# ArduinoMega2560-A4.net
KiCad netlist of a schematic drawn in Altium Designer
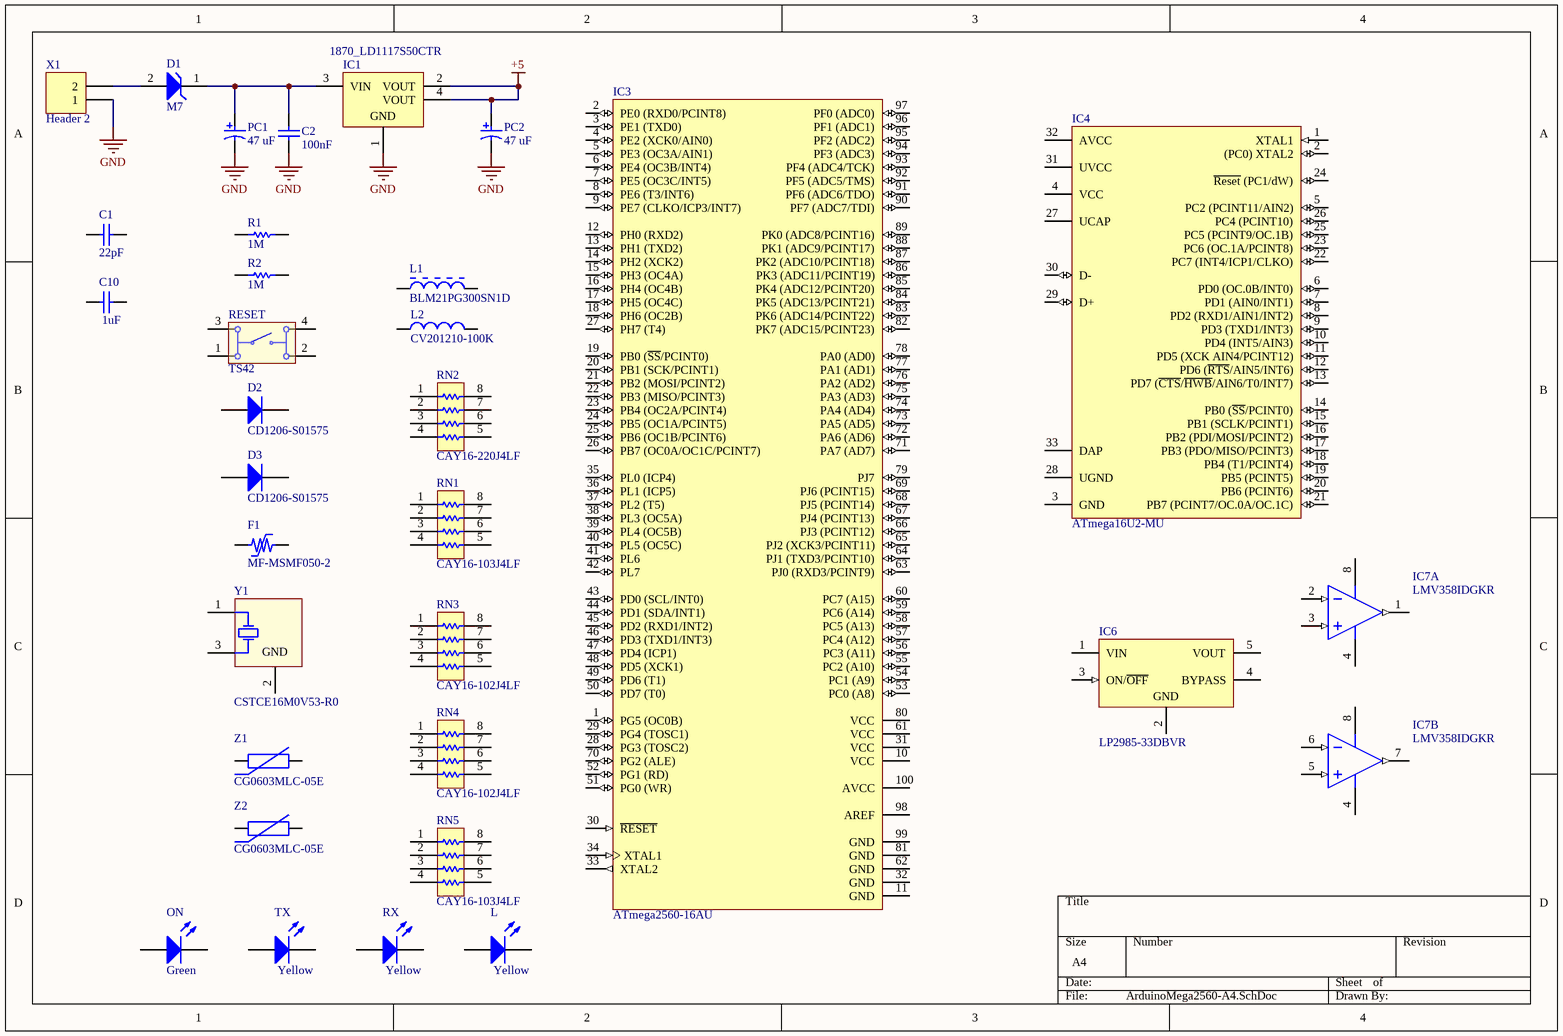
[diagram p0: ArduinoMega2560-A4.SchDoc]

(export (version "E")
  (design (tool "Eeschema 10.0.6"))
  (components
    (comp (ref "C1")
      (value "22pF")
      (footprint "CAPC1608X90X35ML10T15")
      (description "Chip Capacitor, 22 pF, +/- 5%, 50 V, -55 to 125 degC, 0603 (1608 Metric), RoHS, Tape and Reel")
      (fields (field (name "MANUFACTURER") "Murata"))
      (libsource (lib "Altium Content Vault") (part "CAP-NP-2"))
    )
    (comp (ref "C2")
      (value "100nF")
      (footprint "CAPC1608X90X20LL10")
      (description "Chip Capacitor, 0.1 uF, +/- 10%, 50 V, -55 to 125 degC, 0603 (1608 Metric), RoHS, Tape and Reel")
      (fields (field (name "VOLTAGE") "50V") (field (name "TOLERANCE") "10%"))
      (libsource (lib "Altium Content Vault") (part "CAP-NP-2"))
    )
    (comp (ref "C10")
      (value "1uF")
      (footprint "CAPC1608X90X35LL10T15")
      (fields (field (name "MANUFACTURER") "Murata") (field (name "PART NUMBER") "GRM188R61E105KA12D"))
      (libsource (lib "Altium Content Vault") (part "CAP"))
    )
    (comp (ref "D1")
      (value "M7")
      (footprint "ONSC-SMB-2-403A-03_H_V")
      (fields (field (name "PARTNUMBER") "1SMB24AT3G") (field (name "MANUFACTURER") "On Semiconductor"))
      (libsource (lib "Altium Content Vault") (part "ONSC-K1A2-2"))
    )
    (comp (ref "D2")
      (value "CD1206-S01575")
      (footprint "BOUR-CD1206-S01575-2_L")
      (description "75 V Small Signal Switching Diode, 150 mA, 2.5 uA, 1026 Molded Package, RoHS, Tape and Reel")
      (fields (field (name "MANUFACTURER") "Bourns"))
      (libsource (lib "Altium Content Vault") (part "BOUR-A1K2-2"))
    )
    (comp (ref "D3")
      (value "CD1206-S01575")
      (footprint "BOUR-CD1206-S01575-2_L")
      (description "75 V Small Signal Switching Diode, 150 mA, 2.5 uA, 1026 Molded Package, RoHS, Tape and Reel")
      (fields (field (name "MANUFACTURER") "Bourns"))
      (libsource (lib "Altium Content Vault") (part "BOUR-A1K2-2"))
    )
    (comp (ref "F1")
      (value "MF-MSMF050-2")
      (footprint "BOUR-MF-MSMF050-2_V")
      (description "PTC Resettable Fuse, 15 V, 500 mA, -40 to 85 degC, 2-Pin SMD, RoHS, Tape and Reel")
      (fields (field (name "MANUFACTURER") "Bourns"))
      (libsource (lib "Altium Content Vault") (part "PPTC-2"))
    )
    (comp (ref "IC1")
      (value "1870_LD1117S50CTR")
      (footprint "SOT-223_N")
      (libsource (lib "Altium Content Vault") (part "PM-REG-LD1117-SOT4"))
    )
    (comp (ref "IC3")
      (value "ATmega2560-16AU")
      (footprint "100A_M")
      (libsource (lib "Altium Content Vault") (part "MC-8B-ATM640-SQ100"))
    )
    (comp (ref "IC4")
      (value "ATmega16U2-MU")
      (footprint "32PG_N")
      (libsource (lib "Altium Content Vault") (part "MC-8B-ATM8U2-SQ33"))
    )
    (comp (ref "IC6")
      (value "LP2985-33DBVR")
      (footprint "DBV0005A_M")
      (fields (field (name "MANUFACTURER") "Texas Instruments"))
      (libsource (lib "Altium Content Vault") (part "TI-LP2985_A-10DBV5"))
    )
    (comp (ref "IC7")
      (value "LMV358IDGKR")
      (footprint "DGK0008A_M")
      (fields (field (name "MANUFACTURER") "Texas Instruments"))
      (libsource (lib "Altium Content Vault") (part "TI-LMV358-8"))
    )
    (comp (ref "L")
      (value "Yellow")
      (footprint "0805_A")
      (description "0044_KPT-2012YC\r\nLED YELLOW - SMD - 0805\r\nSMD mono-color Chip LED, WL-SMCW, Yellow")
      (fields (field (name "MANUFACTURER") "Wuerth Elektronik") (field (name "PARTNUMBER") "150080YS75000"))
      (libsource (lib "Altium Content Vault") (part "WE-LED_K1A2-2"))
    )
    (comp (ref "L1")
      (value "BLM21PG300SN1D")
      (footprint "MURA-BLM21-B40-CHIP-2_V3")
      (fields (field (name "MANUFACTURER") "Murata"))
      (libsource (lib "Altium Content Vault") (part "MURA-FB-2"))
    )
    (comp (ref "L2")
      (value "CV201210-100K")
      (footprint "MURA-IND0805_L")
      (description "Fixed Inductor, 10 uH, +/-20%, -55 to 125 degC, 2-Pin SMD (0805), RoHS, Tape and Reel")
      (fields (field (name "MANUFACTURER") "Murata"))
      (libsource (lib "Altium Content Vault") (part "IND-2"))
    )
    (comp (ref "ON")
      (value "Green")
      (footprint "0805_A")
      (description "KPT-2012SGC CHIPLED_0805 LED GREEN - SMD-0805\r\nSMD mono-color Chip LED, WL-SMCW, Green")
      (fields (field (name "PARTNUMBER") "150080GS75000") (field (name "MANUFACTURER") "Wuerth Elektronik"))
      (libsource (lib "Altium Content Vault") (part "WE-LED_K1A2-2"))
    )
    (comp (ref "PC1")
      (value "47 uF")
      (footprint "PNSC-FP-V-D_V")
      (fields (field (name "MANUFACTURER") "Panasonic"))
      (libsource (lib "Altium Content Vault") (part "CAP-P-2"))
    )
    (comp (ref "PC2")
      (value "47 uF")
      (footprint "PNSC-FP-V-D_V")
      (fields (field (name "MANUFACTURER") "Panasonic"))
      (libsource (lib "Altium Content Vault") (part "CAP-P-2"))
    )
    (comp (ref "R1")
      (value "1M")
      (footprint "RESC1609X50X30LL10T20")
      (fields (field (name "MANUFACTURER") "Vishay Dale") (field (name "PART NUMBER") "CRCW06031M00FKEA"))
      (libsource (lib "Altium Content Vault") (part "RES"))
    )
    (comp (ref "R2")
      (value "1M")
      (footprint "RESC1609X50X30LL10T20")
      (fields (field (name "MANUFACTURER") "Vishay Dale") (field (name "PART NUMBER") "CRCW06031M00FKEA"))
      (libsource (lib "Altium Content Vault") (part "RES"))
    )
    (comp (ref "RESET")
      (value "TS42")
      (footprint "430152070826")
      (description "WS-TASV SMD Tact Switch 6X6 mm")
      (fields (field (name "PARTNUMBER") "430152070826") (field (name "MANUFACTURER") "Wuerth Elektronik"))
      (libsource (lib "Altium Content Vault") (part "WE-TACT-SW-4"))
    )
    (comp (ref "RN1")
      (value "CAY16-103J4LF")
      (footprint "BOUR-CAY16-J4_V")
      (description "Chip Resistor Array, 10 KOhm, +/- 5%, 62.5 mW, -55 to 125 degC, 8-Pin SMD, RoHS, Tape and Reel")
      (fields (field (name "TOLERANCE") "1%"))
      (libsource (lib "Altium Content Vault") (part "RES-P-8"))
    )
    (comp (ref "RN2")
      (value "CAY16-220J4LF")
      (footprint "BOUR-CAY16-J4_V")
      (description "Chip Resistor Array, 22 Ohm, +/- 5%, 62.5 mW, -55 to 125 degC, 8-Pin SMD, RoHS, Tape and Reel")
      (fields (field (name "TOLERANCE") "1%"))
      (libsource (lib "Altium Content Vault") (part "RES-P-8"))
    )
    (comp (ref "RN3")
      (value "CAY16-102J4LF")
      (footprint "BOUR-CAY16-J4_V")
      (description "Chip Resistor Array, 1 KOhm, +/- 5%, 62.5 mW, -55 to 125 degC, 8-Pin SMD, RoHS, Tape and Reel")
      (fields (field (name "TOLERANCE") "1%"))
      (libsource (lib "Altium Content Vault") (part "RES-P-8"))
    )
    (comp (ref "RN4")
      (value "CAY16-102J4LF")
      (footprint "BOUR-CAY16-J4_V")
      (description "Chip Resistor Array, 1 KOhm, +/- 5%, 62.5 mW, -55 to 125 degC, 8-Pin SMD, RoHS, Tape and Reel")
      (fields (field (name "TOLERANCE") "1%"))
      (libsource (lib "Altium Content Vault") (part "RES-P-8"))
    )
    (comp (ref "RN5")
      (value "CAY16-103J4LF")
      (footprint "BOUR-CAY16-J4_V")
      (description "Chip Resistor Array, 10 KOhm, +/- 5%, 62.5 mW, -55 to 125 degC, 8-Pin SMD, RoHS, Tape and Reel")
      (fields (field (name "TOLERANCE") "1%"))
      (libsource (lib "Altium Content Vault") (part "RES-P-8"))
    )
    (comp (ref "RX")
      (value "Yellow")
      (footprint "0805_A")
      (description "0044_KPT-2012YC\r\nLED YELLOW - SMD - 0805\r\nSMD mono-color Chip LED, WL-SMCW, Yellow")
      (fields (field (name "MANUFACTURER") "Wuerth Elektronik") (field (name "PARTNUMBER") "150080YS75000"))
      (libsource (lib "Altium Content Vault") (part "WE-LED_K1A2-2"))
    )
    (comp (ref "TX")
      (value "Yellow")
      (footprint "0805_A")
      (description "0044_KPT-2012YC\r\nLED YELLOW - SMD - 0805\r\nSMD mono-color Chip LED, WL-SMCW, Yellow")
      (fields (field (name "MANUFACTURER") "Wuerth Elektronik") (field (name "PARTNUMBER") "150080YS75000"))
      (libsource (lib "Altium Content Vault") (part "WE-LED_K1A2-2"))
    )
    (comp (ref "X1")
      (value "Header 2")
      (footprint "HDR1X2")
      (description "Header, 2-Pin")
      (fields (field (name "PUBLISHER") "Altium Limited"))
      (libsource (lib "Miscellaneous Connectors") (part "Header 2"))
    )
    (comp (ref "Y1")
      (value "CSTCE16M0V53-R0")
      (footprint "MURA-CSTCE_V-3_V")
      (fields (field (name "MANUFACTURER") "Murata"))
      (libsource (lib "Altium Content Vault") (part "MURA-CSTCE_V-3"))
    )
    (comp (ref "Z1")
      (value "CG0603MLC-05E")
      (footprint "BOUR-CG0603-2_V")
      (description "ESD Protector, 5 V Supply, -40 to 85 degC, 1.6 x 0.8 x 0.55 mm SMD, RoHS, Tape and Reel")
      (fields (field (name "MANUFACTURER") "Bourns"))
      (libsource (lib "Altium Content Vault") (part "BOUR-VSR-2"))
    )
    (comp (ref "Z2")
      (value "CG0603MLC-05E")
      (footprint "BOUR-CG0603-2_V")
      (description "ESD Protector, 5 V Supply, -40 to 85 degC, 1.6 x 0.8 x 0.55 mm SMD, RoHS, Tape and Reel")
      (fields (field (name "MANUFACTURER") "Bourns"))
      (libsource (lib "Altium Content Vault") (part "BOUR-VSR-2"))
    )
  )
  (nets
    (net (code "1") (name "+5") (class "Default")
      (node (ref "IC1") (pin "2") (pinfunction "VOUT_2") (pintype "power_in"))
      (node (ref "IC1") (pin "4") (pinfunction "VOUT_4") (pintype "power_in"))
      (node (ref "PC2") (pin "1") (pinfunction "1_1") (pintype "passive"))
    )
    (net (code "2") (name "GND") (class "Default")
      (node (ref "C2") (pin "1") (pinfunction "1_1") (pintype "passive"))
      (node (ref "IC1") (pin "1") (pinfunction "GND_1") (pintype "power_in"))
      (node (ref "PC1") (pin "2") (pinfunction "2_2") (pintype "passive"))
      (node (ref "PC2") (pin "2") (pinfunction "2_2") (pintype "passive"))
      (node (ref "X1") (pin "1") (pinfunction "1_1") (pintype "passive"))
    )
    (net (code "3") (name "Net-(D1-A)") (class "Default")
      (node (ref "D1") (pin "2") (pinfunction "A_2") (pintype "passive"))
      (node (ref "X1") (pin "2") (pinfunction "2_2") (pintype "passive"))
    )
    (net (code "4") (name "Net-(D1-K)") (class "Default")
      (node (ref "C2") (pin "2") (pinfunction "2_2") (pintype "passive"))
      (node (ref "D1") (pin "1") (pinfunction "K_1") (pintype "passive"))
      (node (ref "IC1") (pin "3") (pinfunction "VIN_3") (pintype "power_in"))
      (node (ref "PC1") (pin "1") (pinfunction "1_1") (pintype "passive"))
    )
    (net (code "5") (name "unconnected-(C1-Pad1)") (class "Default")
      (node (ref "C1") (pin "1") (pinfunction "1_1") (pintype "passive"))
    )
    (net (code "6") (name "unconnected-(C1-Pad2)") (class "Default")
      (node (ref "C1") (pin "2") (pinfunction "2_2") (pintype "passive"))
    )
    (net (code "7") (name "unconnected-(C10-Pad1)") (class "Default")
      (node (ref "C10") (pin "1") (pinfunction "1_1") (pintype "passive"))
    )
    (net (code "8") (name "unconnected-(C10-Pad2)") (class "Default")
      (node (ref "C10") (pin "2") (pinfunction "2_2") (pintype "passive"))
    )
    (net (code "9") (name "unconnected-(D2-A-Pad1)") (class "Default")
      (node (ref "D2") (pin "1") (pinfunction "A_1") (pintype "passive"))
    )
    (net (code "10") (name "unconnected-(D2-K-Pad2)") (class "Default")
      (node (ref "D2") (pin "2") (pinfunction "K_2") (pintype "passive"))
    )
    (net (code "11") (name "unconnected-(D3-A-Pad1)") (class "Default")
      (node (ref "D3") (pin "1") (pinfunction "A_1") (pintype "passive"))
    )
    (net (code "12") (name "unconnected-(D3-K-Pad2)") (class "Default")
      (node (ref "D3") (pin "2") (pinfunction "K_2") (pintype "passive"))
    )
    (net (code "13") (name "unconnected-(F1-Pad1)") (class "Default")
      (node (ref "F1") (pin "1") (pinfunction "1_1") (pintype "passive"))
    )
    (net (code "14") (name "unconnected-(F1-Pad2)") (class "Default")
      (node (ref "F1") (pin "2") (pinfunction "2_2") (pintype "passive"))
    )
    (net (code "15") (name "unconnected-(IC3-AREF-Pad98)") (class "Default")
      (node (ref "IC3") (pin "98") (pinfunction "AREF_98") (pintype "power_in"))
    )
    (net (code "16") (name "unconnected-(IC3-AVCC-Pad100)") (class "Default")
      (node (ref "IC3") (pin "100") (pinfunction "AVCC_100") (pintype "power_in"))
    )
    (net (code "17") (name "unconnected-(IC3-GND-Pad11)") (class "Default")
      (node (ref "IC3") (pin "11") (pinfunction "GND_11") (pintype "power_in"))
    )
    (net (code "18") (name "unconnected-(IC3-GND-Pad32)") (class "Default")
      (node (ref "IC3") (pin "32") (pinfunction "GND_32") (pintype "power_in"))
    )
    (net (code "19") (name "unconnected-(IC3-GND-Pad62)") (class "Default")
      (node (ref "IC3") (pin "62") (pinfunction "GND_62") (pintype "power_in"))
    )
    (net (code "20") (name "unconnected-(IC3-GND-Pad81)") (class "Default")
      (node (ref "IC3") (pin "81") (pinfunction "GND_81") (pintype "power_in"))
    )
    (net (code "21") (name "unconnected-(IC3-GND-Pad99)") (class "Default")
      (node (ref "IC3") (pin "99") (pinfunction "GND_99") (pintype "power_in"))
    )
    (net (code "22") (name "unconnected-(IC3-PA0_(AD0)-Pad78)") (class "Default")
      (node (ref "IC3") (pin "78") (pinfunction "PA0_(AD0)_78") (pintype "bidirectional"))
    )
    (net (code "23") (name "unconnected-(IC3-PA1_(AD1)-Pad77)") (class "Default")
      (node (ref "IC3") (pin "77") (pinfunction "PA1_(AD1)_77") (pintype "bidirectional"))
    )
    (net (code "24") (name "unconnected-(IC3-PA2_(AD2)-Pad76)") (class "Default")
      (node (ref "IC3") (pin "76") (pinfunction "PA2_(AD2)_76") (pintype "bidirectional"))
    )
    (net (code "25") (name "unconnected-(IC3-PA3_(AD3)-Pad75)") (class "Default")
      (node (ref "IC3") (pin "75") (pinfunction "PA3_(AD3)_75") (pintype "bidirectional"))
    )
    (net (code "26") (name "unconnected-(IC3-PA4_(AD4)-Pad74)") (class "Default")
      (node (ref "IC3") (pin "74") (pinfunction "PA4_(AD4)_74") (pintype "bidirectional"))
    )
    (net (code "27") (name "unconnected-(IC3-PA5_(AD5)-Pad73)") (class "Default")
      (node (ref "IC3") (pin "73") (pinfunction "PA5_(AD5)_73") (pintype "bidirectional"))
    )
    (net (code "28") (name "unconnected-(IC3-PA6_(AD6)-Pad72)") (class "Default")
      (node (ref "IC3") (pin "72") (pinfunction "PA6_(AD6)_72") (pintype "bidirectional"))
    )
    (net (code "29") (name "unconnected-(IC3-PA7_(AD7)-Pad71)") (class "Default")
      (node (ref "IC3") (pin "71") (pinfunction "PA7_(AD7)_71") (pintype "bidirectional"))
    )
    (net (code "30") (name "unconnected-(IC3-PB0_(~{SS}{slash}PCINT0)-Pad19)") (class "Default")
      (node (ref "IC3") (pin "19") (pinfunction "PB0_(~{SS}/PCINT0)_19") (pintype "bidirectional"))
    )
    (net (code "31") (name "unconnected-(IC3-PB1_(SCK{slash}PCINT1)-Pad20)") (class "Default")
      (node (ref "IC3") (pin "20") (pinfunction "PB1_(SCK/PCINT1)_20") (pintype "bidirectional"))
    )
    (net (code "32") (name "unconnected-(IC3-PB2_(MOSI{slash}PCINT2)-Pad21)") (class "Default")
      (node (ref "IC3") (pin "21") (pinfunction "PB2_(MOSI/PCINT2)_21") (pintype "bidirectional"))
    )
    (net (code "33") (name "unconnected-(IC3-PB3_(MISO{slash}PCINT3)-Pad22)") (class "Default")
      (node (ref "IC3") (pin "22") (pinfunction "PB3_(MISO/PCINT3)_22") (pintype "bidirectional"))
    )
    (net (code "34") (name "unconnected-(IC3-PB4_(OC2A{slash}PCINT4)-Pad23)") (class "Default")
      (node (ref "IC3") (pin "23") (pinfunction "PB4_(OC2A/PCINT4)_23") (pintype "bidirectional"))
    )
    (net (code "35") (name "unconnected-(IC3-PB5_(OC1A{slash}PCINT5)-Pad24)") (class "Default")
      (node (ref "IC3") (pin "24") (pinfunction "PB5_(OC1A/PCINT5)_24") (pintype "bidirectional"))
    )
    (net (code "36") (name "unconnected-(IC3-PB6_(OC1B{slash}PCINT6)-Pad25)") (class "Default")
      (node (ref "IC3") (pin "25") (pinfunction "PB6_(OC1B/PCINT6)_25") (pintype "bidirectional"))
    )
    (net (code "37") (name "unconnected-(IC3-PB7_(OC0A{slash}OC1C{slash}PCINT7)-Pad26)") (class "Default")
      (node (ref "IC3") (pin "26") (pinfunction "PB7_(OC0A/OC1C/PCINT7)_26") (pintype "bidirectional"))
    )
    (net (code "38") (name "unconnected-(IC3-PC0_(A8)-Pad53)") (class "Default")
      (node (ref "IC3") (pin "53") (pinfunction "PC0_(A8)_53") (pintype "bidirectional"))
    )
    (net (code "39") (name "unconnected-(IC3-PC1_(A9)-Pad54)") (class "Default")
      (node (ref "IC3") (pin "54") (pinfunction "PC1_(A9)_54") (pintype "bidirectional"))
    )
    (net (code "40") (name "unconnected-(IC3-PC2_(A10)-Pad55)") (class "Default")
      (node (ref "IC3") (pin "55") (pinfunction "PC2_(A10)_55") (pintype "bidirectional"))
    )
    (net (code "41") (name "unconnected-(IC3-PC3_(A11)-Pad56)") (class "Default")
      (node (ref "IC3") (pin "56") (pinfunction "PC3_(A11)_56") (pintype "bidirectional"))
    )
    (net (code "42") (name "unconnected-(IC3-PC4_(A12)-Pad57)") (class "Default")
      (node (ref "IC3") (pin "57") (pinfunction "PC4_(A12)_57") (pintype "bidirectional"))
    )
    (net (code "43") (name "unconnected-(IC3-PC5_(A13)-Pad58)") (class "Default")
      (node (ref "IC3") (pin "58") (pinfunction "PC5_(A13)_58") (pintype "bidirectional"))
    )
    (net (code "44") (name "unconnected-(IC3-PC6_(A14)-Pad59)") (class "Default")
      (node (ref "IC3") (pin "59") (pinfunction "PC6_(A14)_59") (pintype "bidirectional"))
    )
    (net (code "45") (name "unconnected-(IC3-PC7_(A15)-Pad60)") (class "Default")
      (node (ref "IC3") (pin "60") (pinfunction "PC7_(A15)_60") (pintype "bidirectional"))
    )
    (net (code "46") (name "unconnected-(IC3-PD0_(SCL{slash}INT0)-Pad43)") (class "Default")
      (node (ref "IC3") (pin "43") (pinfunction "PD0_(SCL/INT0)_43") (pintype "bidirectional"))
    )
    (net (code "47") (name "unconnected-(IC3-PD1_(SDA{slash}INT1)-Pad44)") (class "Default")
      (node (ref "IC3") (pin "44") (pinfunction "PD1_(SDA/INT1)_44") (pintype "bidirectional"))
    )
    (net (code "48") (name "unconnected-(IC3-PD2_(RXD1{slash}INT2)-Pad45)") (class "Default")
      (node (ref "IC3") (pin "45") (pinfunction "PD2_(RXD1/INT2)_45") (pintype "bidirectional"))
    )
    (net (code "49") (name "unconnected-(IC3-PD3_(TXD1{slash}INT3)-Pad46)") (class "Default")
      (node (ref "IC3") (pin "46") (pinfunction "PD3_(TXD1/INT3)_46") (pintype "bidirectional"))
    )
    (net (code "50") (name "unconnected-(IC3-PD4_(ICP1)-Pad47)") (class "Default")
      (node (ref "IC3") (pin "47") (pinfunction "PD4_(ICP1)_47") (pintype "bidirectional"))
    )
    (net (code "51") (name "unconnected-(IC3-PD5_(XCK1)-Pad48)") (class "Default")
      (node (ref "IC3") (pin "48") (pinfunction "PD5_(XCK1)_48") (pintype "bidirectional"))
    )
    (net (code "52") (name "unconnected-(IC3-PD6_(T1)-Pad49)") (class "Default")
      (node (ref "IC3") (pin "49") (pinfunction "PD6_(T1)_49") (pintype "bidirectional"))
    )
    (net (code "53") (name "unconnected-(IC3-PD7_(T0)-Pad50)") (class "Default")
      (node (ref "IC3") (pin "50") (pinfunction "PD7_(T0)_50") (pintype "bidirectional"))
    )
    (net (code "54") (name "unconnected-(IC3-PE0_(RXD0{slash}PCINT8)-Pad2)") (class "Default")
      (node (ref "IC3") (pin "2") (pinfunction "PE0_(RXD0/PCINT8)_2") (pintype "bidirectional"))
    )
    (net (code "55") (name "unconnected-(IC3-PE1_(TXD0)-Pad3)") (class "Default")
      (node (ref "IC3") (pin "3") (pinfunction "PE1_(TXD0)_3") (pintype "bidirectional"))
    )
    (net (code "56") (name "unconnected-(IC3-PE2_(XCK0{slash}AIN0)-Pad4)") (class "Default")
      (node (ref "IC3") (pin "4") (pinfunction "PE2_(XCK0/AIN0)_4") (pintype "bidirectional"))
    )
    (net (code "57") (name "unconnected-(IC3-PE3_(OC3A{slash}AIN1)-Pad5)") (class "Default")
      (node (ref "IC3") (pin "5") (pinfunction "PE3_(OC3A/AIN1)_5") (pintype "bidirectional"))
    )
    (net (code "58") (name "unconnected-(IC3-PE4_(OC3B{slash}INT4)-Pad6)") (class "Default")
      (node (ref "IC3") (pin "6") (pinfunction "PE4_(OC3B/INT4)_6") (pintype "bidirectional"))
    )
    (net (code "59") (name "unconnected-(IC3-PE5_(OC3C{slash}INT5)-Pad7)") (class "Default")
      (node (ref "IC3") (pin "7") (pinfunction "PE5_(OC3C/INT5)_7") (pintype "bidirectional"))
    )
    (net (code "60") (name "unconnected-(IC3-PE6_(T3{slash}INT6)-Pad8)") (class "Default")
      (node (ref "IC3") (pin "8") (pinfunction "PE6_(T3/INT6)_8") (pintype "bidirectional"))
    )
    (net (code "61") (name "unconnected-(IC3-PE7_(CLKO{slash}ICP3{slash}INT7)-Pad9)") (class "Default")
      (node (ref "IC3") (pin "9") (pinfunction "PE7_(CLKO/ICP3/INT7)_9") (pintype "bidirectional"))
    )
    (net (code "62") (name "unconnected-(IC3-PF0_(ADC0)-Pad97)") (class "Default")
      (node (ref "IC3") (pin "97") (pinfunction "PF0_(ADC0)_97") (pintype "bidirectional"))
    )
    (net (code "63") (name "unconnected-(IC3-PF1_(ADC1)-Pad96)") (class "Default")
      (node (ref "IC3") (pin "96") (pinfunction "PF1_(ADC1)_96") (pintype "bidirectional"))
    )
    (net (code "64") (name "unconnected-(IC3-PF2_(ADC2)-Pad95)") (class "Default")
      (node (ref "IC3") (pin "95") (pinfunction "PF2_(ADC2)_95") (pintype "bidirectional"))
    )
    (net (code "65") (name "unconnected-(IC3-PF3_(ADC3)-Pad94)") (class "Default")
      (node (ref "IC3") (pin "94") (pinfunction "PF3_(ADC3)_94") (pintype "bidirectional"))
    )
    (net (code "66") (name "unconnected-(IC3-PF4_(ADC4{slash}TCK)-Pad93)") (class "Default")
      (node (ref "IC3") (pin "93") (pinfunction "PF4_(ADC4/TCK)_93") (pintype "bidirectional"))
    )
    (net (code "67") (name "unconnected-(IC3-PF5_(ADC5{slash}TMS)-Pad92)") (class "Default")
      (node (ref "IC3") (pin "92") (pinfunction "PF5_(ADC5/TMS)_92") (pintype "bidirectional"))
    )
    (net (code "68") (name "unconnected-(IC3-PF6_(ADC6{slash}TDO)-Pad91)") (class "Default")
      (node (ref "IC3") (pin "91") (pinfunction "PF6_(ADC6/TDO)_91") (pintype "bidirectional"))
    )
    (net (code "69") (name "unconnected-(IC3-PF7_(ADC7{slash}TDI)-Pad90)") (class "Default")
      (node (ref "IC3") (pin "90") (pinfunction "PF7_(ADC7/TDI)_90") (pintype "bidirectional"))
    )
    (net (code "70") (name "unconnected-(IC3-PG0_(WR)-Pad51)") (class "Default")
      (node (ref "IC3") (pin "51") (pinfunction "PG0_(WR)_51") (pintype "bidirectional"))
    )
    (net (code "71") (name "unconnected-(IC3-PG1_(RD)-Pad52)") (class "Default")
      (node (ref "IC3") (pin "52") (pinfunction "PG1_(RD)_52") (pintype "bidirectional"))
    )
    (net (code "72") (name "unconnected-(IC3-PG2_(ALE)-Pad70)") (class "Default")
      (node (ref "IC3") (pin "70") (pinfunction "PG2_(ALE)_70") (pintype "bidirectional"))
    )
    (net (code "73") (name "unconnected-(IC3-PG3_(TOSC2)-Pad28)") (class "Default")
      (node (ref "IC3") (pin "28") (pinfunction "PG3_(TOSC2)_28") (pintype "bidirectional"))
    )
    (net (code "74") (name "unconnected-(IC3-PG4_(TOSC1)-Pad29)") (class "Default")
      (node (ref "IC3") (pin "29") (pinfunction "PG4_(TOSC1)_29") (pintype "bidirectional"))
    )
    (net (code "75") (name "unconnected-(IC3-PG5_(OC0B)-Pad1)") (class "Default")
      (node (ref "IC3") (pin "1") (pinfunction "PG5_(OC0B)_1") (pintype "bidirectional"))
    )
    (net (code "76") (name "unconnected-(IC3-PH0_(RXD2)-Pad12)") (class "Default")
      (node (ref "IC3") (pin "12") (pinfunction "PH0_(RXD2)_12") (pintype "bidirectional"))
    )
    (net (code "77") (name "unconnected-(IC3-PH1_(TXD2)-Pad13)") (class "Default")
      (node (ref "IC3") (pin "13") (pinfunction "PH1_(TXD2)_13") (pintype "bidirectional"))
    )
    (net (code "78") (name "unconnected-(IC3-PH2_(XCK2)-Pad14)") (class "Default")
      (node (ref "IC3") (pin "14") (pinfunction "PH2_(XCK2)_14") (pintype "bidirectional"))
    )
    (net (code "79") (name "unconnected-(IC3-PH3_(OC4A)-Pad15)") (class "Default")
      (node (ref "IC3") (pin "15") (pinfunction "PH3_(OC4A)_15") (pintype "bidirectional"))
    )
    (net (code "80") (name "unconnected-(IC3-PH4_(OC4B)-Pad16)") (class "Default")
      (node (ref "IC3") (pin "16") (pinfunction "PH4_(OC4B)_16") (pintype "bidirectional"))
    )
    (net (code "81") (name "unconnected-(IC3-PH5_(OC4C)-Pad17)") (class "Default")
      (node (ref "IC3") (pin "17") (pinfunction "PH5_(OC4C)_17") (pintype "bidirectional"))
    )
    (net (code "82") (name "unconnected-(IC3-PH6_(OC2B)-Pad18)") (class "Default")
      (node (ref "IC3") (pin "18") (pinfunction "PH6_(OC2B)_18") (pintype "bidirectional"))
    )
    (net (code "83") (name "unconnected-(IC3-PH7_(T4)-Pad27)") (class "Default")
      (node (ref "IC3") (pin "27") (pinfunction "PH7_(T4)_27") (pintype "bidirectional"))
    )
    (net (code "84") (name "unconnected-(IC3-PJ0_(RXD3{slash}PCINT9)-Pad63)") (class "Default")
      (node (ref "IC3") (pin "63") (pinfunction "PJ0_(RXD3/PCINT9)_63") (pintype "bidirectional"))
    )
    (net (code "85") (name "unconnected-(IC3-PJ1_(TXD3{slash}PCINT10)-Pad64)") (class "Default")
      (node (ref "IC3") (pin "64") (pinfunction "PJ1_(TXD3/PCINT10)_64") (pintype "bidirectional"))
    )
    (net (code "86") (name "unconnected-(IC3-PJ2_(XCK3{slash}PCINT11)-Pad65)") (class "Default")
      (node (ref "IC3") (pin "65") (pinfunction "PJ2_(XCK3/PCINT11)_65") (pintype "bidirectional"))
    )
    (net (code "87") (name "unconnected-(IC3-PJ3_(PCINT12)-Pad66)") (class "Default")
      (node (ref "IC3") (pin "66") (pinfunction "PJ3_(PCINT12)_66") (pintype "bidirectional"))
    )
    (net (code "88") (name "unconnected-(IC3-PJ4_(PCINT13)-Pad67)") (class "Default")
      (node (ref "IC3") (pin "67") (pinfunction "PJ4_(PCINT13)_67") (pintype "bidirectional"))
    )
    (net (code "89") (name "unconnected-(IC3-PJ5_(PCINT14)-Pad68)") (class "Default")
      (node (ref "IC3") (pin "68") (pinfunction "PJ5_(PCINT14)_68") (pintype "bidirectional"))
    )
    (net (code "90") (name "unconnected-(IC3-PJ6_(PCINT15)-Pad69)") (class "Default")
      (node (ref "IC3") (pin "69") (pinfunction "PJ6_(PCINT15)_69") (pintype "bidirectional"))
    )
    (net (code "91") (name "unconnected-(IC3-PJ7-Pad79)") (class "Default")
      (node (ref "IC3") (pin "79") (pinfunction "PJ7_79") (pintype "bidirectional"))
    )
    (net (code "92") (name "unconnected-(IC3-PK0_(ADC8{slash}PCINT16)-Pad89)") (class "Default")
      (node (ref "IC3") (pin "89") (pinfunction "PK0_(ADC8/PCINT16)_89") (pintype "bidirectional"))
    )
    (net (code "93") (name "unconnected-(IC3-PK1_(ADC9{slash}PCINT17)-Pad88)") (class "Default")
      (node (ref "IC3") (pin "88") (pinfunction "PK1_(ADC9/PCINT17)_88") (pintype "bidirectional"))
    )
    (net (code "94") (name "unconnected-(IC3-PK2_(ADC10{slash}PCINT18)-Pad87)") (class "Default")
      (node (ref "IC3") (pin "87") (pinfunction "PK2_(ADC10/PCINT18)_87") (pintype "bidirectional"))
    )
    (net (code "95") (name "unconnected-(IC3-PK3_(ADC11{slash}PCINT19)-Pad86)") (class "Default")
      (node (ref "IC3") (pin "86") (pinfunction "PK3_(ADC11/PCINT19)_86") (pintype "bidirectional"))
    )
    (net (code "96") (name "unconnected-(IC3-PK4_(ADC12{slash}PCINT20)-Pad85)") (class "Default")
      (node (ref "IC3") (pin "85") (pinfunction "PK4_(ADC12/PCINT20)_85") (pintype "bidirectional"))
    )
    (net (code "97") (name "unconnected-(IC3-PK5_(ADC13{slash}PCINT21)-Pad84)") (class "Default")
      (node (ref "IC3") (pin "84") (pinfunction "PK5_(ADC13/PCINT21)_84") (pintype "bidirectional"))
    )
    (net (code "98") (name "unconnected-(IC3-PK6_(ADC14{slash}PCINT22)-Pad83)") (class "Default")
      (node (ref "IC3") (pin "83") (pinfunction "PK6_(ADC14/PCINT22)_83") (pintype "bidirectional"))
    )
    (net (code "99") (name "unconnected-(IC3-PK7_(ADC15{slash}PCINT23)-Pad82)") (class "Default")
      (node (ref "IC3") (pin "82") (pinfunction "PK7_(ADC15/PCINT23)_82") (pintype "bidirectional"))
    )
    (net (code "100") (name "unconnected-(IC3-PL0_(ICP4)-Pad35)") (class "Default")
      (node (ref "IC3") (pin "35") (pinfunction "PL0_(ICP4)_35") (pintype "bidirectional"))
    )
    (net (code "101") (name "unconnected-(IC3-PL1_(ICP5)-Pad36)") (class "Default")
      (node (ref "IC3") (pin "36") (pinfunction "PL1_(ICP5)_36") (pintype "bidirectional"))
    )
    (net (code "102") (name "unconnected-(IC3-PL2_(T5)-Pad37)") (class "Default")
      (node (ref "IC3") (pin "37") (pinfunction "PL2_(T5)_37") (pintype "bidirectional"))
    )
    (net (code "103") (name "unconnected-(IC3-PL3_(OC5A)-Pad38)") (class "Default")
      (node (ref "IC3") (pin "38") (pinfunction "PL3_(OC5A)_38") (pintype "bidirectional"))
    )
    (net (code "104") (name "unconnected-(IC3-PL4_(OC5B)-Pad39)") (class "Default")
      (node (ref "IC3") (pin "39") (pinfunction "PL4_(OC5B)_39") (pintype "bidirectional"))
    )
    (net (code "105") (name "unconnected-(IC3-PL5_(OC5C)-Pad40)") (class "Default")
      (node (ref "IC3") (pin "40") (pinfunction "PL5_(OC5C)_40") (pintype "bidirectional"))
    )
    (net (code "106") (name "unconnected-(IC3-PL6-Pad41)") (class "Default")
      (node (ref "IC3") (pin "41") (pinfunction "PL6_41") (pintype "bidirectional"))
    )
    (net (code "107") (name "unconnected-(IC3-PL7-Pad42)") (class "Default")
      (node (ref "IC3") (pin "42") (pinfunction "PL7_42") (pintype "bidirectional"))
    )
    (net (code "108") (name "unconnected-(IC3-VCC-Pad10)") (class "Default")
      (node (ref "IC3") (pin "10") (pinfunction "VCC_10") (pintype "power_in"))
    )
    (net (code "109") (name "unconnected-(IC3-VCC-Pad31)") (class "Default")
      (node (ref "IC3") (pin "31") (pinfunction "VCC_31") (pintype "power_in"))
    )
    (net (code "110") (name "unconnected-(IC3-VCC-Pad61)") (class "Default")
      (node (ref "IC3") (pin "61") (pinfunction "VCC_61") (pintype "power_in"))
    )
    (net (code "111") (name "unconnected-(IC3-VCC-Pad80)") (class "Default")
      (node (ref "IC3") (pin "80") (pinfunction "VCC_80") (pintype "power_in"))
    )
    (net (code "112") (name "unconnected-(IC3-XTAL1-Pad34)") (class "Default")
      (node (ref "IC3") (pin "34") (pinfunction "XTAL1_34") (pintype "input"))
    )
    (net (code "113") (name "unconnected-(IC3-XTAL2-Pad33)") (class "Default")
      (node (ref "IC3") (pin "33") (pinfunction "XTAL2_33") (pintype "output"))
    )
    (net (code "114") (name "unconnected-(IC3-~{RESET}-Pad30)") (class "Default")
      (node (ref "IC3") (pin "30") (pinfunction "~{RESET}_30") (pintype "input"))
    )
    (net (code "115") (name "unconnected-(IC4-(PC0)_XTAL2-Pad2)") (class "Default")
      (node (ref "IC4") (pin "2") (pinfunction "(PC0)_XTAL2_2") (pintype "bidirectional"))
    )
    (net (code "116") (name "unconnected-(IC4-AVCC-Pad32)") (class "Default")
      (node (ref "IC4") (pin "32") (pinfunction "AVCC_32") (pintype "power_in"))
    )
    (net (code "117") (name "unconnected-(IC4-D+-Pad29)") (class "Default")
      (node (ref "IC4") (pin "29") (pinfunction "D+_29") (pintype "bidirectional"))
    )
    (net (code "118") (name "unconnected-(IC4-D--Pad30)") (class "Default")
      (node (ref "IC4") (pin "30") (pinfunction "D-_30") (pintype "bidirectional"))
    )
    (net (code "119") (name "unconnected-(IC4-DAP-Pad33)") (class "Default")
      (node (ref "IC4") (pin "33") (pinfunction "DAP_33") (pintype "power_in"))
    )
    (net (code "120") (name "unconnected-(IC4-GND-Pad3)") (class "Default")
      (node (ref "IC4") (pin "3") (pinfunction "GND_3") (pintype "power_in"))
    )
    (net (code "121") (name "unconnected-(IC4-PB0_(~{SS}{slash}PCINT0)-Pad14)") (class "Default")
      (node (ref "IC4") (pin "14") (pinfunction "PB0_(~{SS}/PCINT0)_14") (pintype "bidirectional"))
    )
    (net (code "122") (name "unconnected-(IC4-PB1_(SCLK{slash}PCINT1)-Pad15)") (class "Default")
      (node (ref "IC4") (pin "15") (pinfunction "PB1_(SCLK/PCINT1)_15") (pintype "bidirectional"))
    )
    (net (code "123") (name "unconnected-(IC4-PB2_(PDI{slash}MOSI{slash}PCINT2)-Pad16)") (class "Default")
      (node (ref "IC4") (pin "16") (pinfunction "PB2_(PDI/MOSI/PCINT2)_16") (pintype "bidirectional"))
    )
    (net (code "124") (name "unconnected-(IC4-PB3_(PDO{slash}MISO{slash}PCINT3)-Pad17)") (class "Default")
      (node (ref "IC4") (pin "17") (pinfunction "PB3_(PDO/MISO/PCINT3)_17") (pintype "bidirectional"))
    )
    (net (code "125") (name "unconnected-(IC4-PB4_(T1{slash}PCINT4)-Pad18)") (class "Default")
      (node (ref "IC4") (pin "18") (pinfunction "PB4_(T1/PCINT4)_18") (pintype "bidirectional"))
    )
    (net (code "126") (name "unconnected-(IC4-PB5_(PCINT5)-Pad19)") (class "Default")
      (node (ref "IC4") (pin "19") (pinfunction "PB5_(PCINT5)_19") (pintype "bidirectional"))
    )
    (net (code "127") (name "unconnected-(IC4-PB6_(PCINT6)-Pad20)") (class "Default")
      (node (ref "IC4") (pin "20") (pinfunction "PB6_(PCINT6)_20") (pintype "bidirectional"))
    )
    (net (code "128") (name "unconnected-(IC4-PB7_(PCINT7{slash}OC.0A{slash}OC.1C)-Pad21)") (class "Default")
      (node (ref "IC4") (pin "21") (pinfunction "PB7_(PCINT7/OC.0A/OC.1C)_21") (pintype "bidirectional"))
    )
    (net (code "129") (name "unconnected-(IC4-PC2_(PCINT11{slash}AIN2)-Pad5)") (class "Default")
      (node (ref "IC4") (pin "5") (pinfunction "PC2_(PCINT11/AIN2)_5") (pintype "bidirectional"))
    )
    (net (code "130") (name "unconnected-(IC4-PC4_(PCINT10)-Pad26)") (class "Default")
      (node (ref "IC4") (pin "26") (pinfunction "PC4_(PCINT10)_26") (pintype "bidirectional"))
    )
    (net (code "131") (name "unconnected-(IC4-PC5_(PCINT9{slash}OC.1B)-Pad25)") (class "Default")
      (node (ref "IC4") (pin "25") (pinfunction "PC5_(PCINT9/OC.1B)_25") (pintype "bidirectional"))
    )
    (net (code "132") (name "unconnected-(IC4-PC6_(OC.1A{slash}PCINT8)-Pad23)") (class "Default")
      (node (ref "IC4") (pin "23") (pinfunction "PC6_(OC.1A/PCINT8)_23") (pintype "bidirectional"))
    )
    (net (code "133") (name "unconnected-(IC4-PC7_(INT4{slash}ICP1{slash}CLKO)-Pad22)") (class "Default")
      (node (ref "IC4") (pin "22") (pinfunction "PC7_(INT4/ICP1/CLKO)_22") (pintype "bidirectional"))
    )
    (net (code "134") (name "unconnected-(IC4-PD0_(OC.0B{slash}INT0)-Pad6)") (class "Default")
      (node (ref "IC4") (pin "6") (pinfunction "PD0_(OC.0B/INT0)_6") (pintype "bidirectional"))
    )
    (net (code "135") (name "unconnected-(IC4-PD1_(AIN0{slash}INT1)-Pad7)") (class "Default")
      (node (ref "IC4") (pin "7") (pinfunction "PD1_(AIN0/INT1)_7") (pintype "bidirectional"))
    )
    (net (code "136") (name "unconnected-(IC4-PD2_(RXD1{slash}AIN1{slash}INT2)-Pad8)") (class "Default")
      (node (ref "IC4") (pin "8") (pinfunction "PD2_(RXD1/AIN1/INT2)_8") (pintype "bidirectional"))
    )
    (net (code "137") (name "unconnected-(IC4-PD3_(TXD1{slash}INT3)-Pad9)") (class "Default")
      (node (ref "IC4") (pin "9") (pinfunction "PD3_(TXD1/INT3)_9") (pintype "bidirectional"))
    )
    (net (code "138") (name "unconnected-(IC4-PD4_(INT5{slash}AIN3)-Pad10)") (class "Default")
      (node (ref "IC4") (pin "10") (pinfunction "PD4_(INT5/AIN3)_10") (pintype "bidirectional"))
    )
    (net (code "139") (name "unconnected-(IC4-PD5_(XCK_AIN4{slash}PCINT12)-Pad11)") (class "Default")
      (node (ref "IC4") (pin "11") (pinfunction "PD5_(XCK_AIN4/PCINT12)_11") (pintype "bidirectional"))
    )
    (net (code "140") (name "unconnected-(IC4-PD6_(~{RTS}{slash}AIN5{slash}INT6)-Pad12)") (class "Default")
      (node (ref "IC4") (pin "12") (pinfunction "PD6_(~{RTS}/AIN5/INT6)_12") (pintype "bidirectional"))
    )
    (net (code "141") (name "unconnected-(IC4-PD7_(~{CTS}{slash}~{HWB}{slash}AIN6{slash}T0{slash}INT7)-Pad13)") (class "Default")
      (node (ref "IC4") (pin "13") (pinfunction "PD7_(~{CTS}/~{HWB}/AIN6/T0/INT7)_13") (pintype "bidirectional"))
    )
    (net (code "142") (name "unconnected-(IC4-UCAP-Pad27)") (class "Default")
      (node (ref "IC4") (pin "27") (pinfunction "UCAP_27") (pintype "power_in"))
    )
    (net (code "143") (name "unconnected-(IC4-UGND-Pad28)") (class "Default")
      (node (ref "IC4") (pin "28") (pinfunction "UGND_28") (pintype "power_in"))
    )
    (net (code "144") (name "unconnected-(IC4-UVCC-Pad31)") (class "Default")
      (node (ref "IC4") (pin "31") (pinfunction "UVCC_31") (pintype "power_in"))
    )
    (net (code "145") (name "unconnected-(IC4-VCC-Pad4)") (class "Default")
      (node (ref "IC4") (pin "4") (pinfunction "VCC_4") (pintype "power_in"))
    )
    (net (code "146") (name "unconnected-(IC4-XTAL1-Pad1)") (class "Default")
      (node (ref "IC4") (pin "1") (pinfunction "XTAL1_1") (pintype "input"))
    )
    (net (code "147") (name "unconnected-(IC4-~{Reset}_(PC1{slash}dW)-Pad24)") (class "Default")
      (node (ref "IC4") (pin "24") (pinfunction "~{Reset}_(PC1/dW)_24") (pintype "bidirectional"))
    )
    (net (code "148") (name "unconnected-(IC6-BYPASS-Pad4)") (class "Default")
      (node (ref "IC6") (pin "4") (pinfunction "BYPASS_4") (pintype "passive"))
    )
    (net (code "149") (name "unconnected-(IC6-GND-Pad2)") (class "Default")
      (node (ref "IC6") (pin "2") (pinfunction "GND_2") (pintype "power_in"))
    )
    (net (code "150") (name "unconnected-(IC6-ON{slash}~{OFF}-Pad3)") (class "Default")
      (node (ref "IC6") (pin "3") (pinfunction "ON/~{OFF}_3") (pintype "input"))
    )
    (net (code "151") (name "unconnected-(IC6-VIN-Pad1)") (class "Default")
      (node (ref "IC6") (pin "1") (pinfunction "VIN_1") (pintype "power_in"))
    )
    (net (code "152") (name "unconnected-(IC6-VOUT-Pad5)") (class "Default")
      (node (ref "IC6") (pin "5") (pinfunction "VOUT_5") (pintype "power_in"))
    )
    (net (code "153") (name "unconnected-(IC7A-1IN+-Pad3)") (class "Default")
      (node (ref "IC7") (pin "3") (pinfunction "1IN+_3") (pintype "input"))
    )
    (net (code "154") (name "unconnected-(IC7A-1IN--Pad2)") (class "Default")
      (node (ref "IC7") (pin "2") (pinfunction "1IN-_2") (pintype "input"))
    )
    (net (code "155") (name "unconnected-(IC7A-1OUT-Pad1)") (class "Default")
      (node (ref "IC7") (pin "1") (pinfunction "1OUT_1") (pintype "output"))
    )
    (net (code "156") (name "unconnected-(IC7A-GND-Pad4)") (class "Default")
      (node (ref "IC7") (pin "4") (pinfunction "GND_4") (pintype "power_in"))
    )
    (net (code "157") (name "unconnected-(IC7A-VCC+-Pad8)") (class "Default")
      (node (ref "IC7") (pin "8") (pinfunction "VCC+_8") (pintype "power_in"))
    )
    (net (code "158") (name "unconnected-(IC7B-2IN+-Pad5)") (class "Default")
      (node (ref "IC7") (pin "5") (pinfunction "2IN+_5") (pintype "input"))
    )
    (net (code "159") (name "unconnected-(IC7B-2IN--Pad6)") (class "Default")
      (node (ref "IC7") (pin "6") (pinfunction "2IN-_6") (pintype "input"))
    )
    (net (code "160") (name "unconnected-(IC7B-2OUT-Pad7)") (class "Default")
      (node (ref "IC7") (pin "7") (pinfunction "2OUT_7") (pintype "output"))
    )
    (net (code "161") (name "unconnected-(IC7B-GND-Pad4)") (class "Default")
      (node (ref "IC7") (pin "4") (pinfunction "GND_4") (pintype "power_in"))
    )
    (net (code "162") (name "unconnected-(IC7B-VCC+-Pad8)") (class "Default")
      (node (ref "IC7") (pin "8") (pinfunction "VCC+_8") (pintype "power_in"))
    )
    (net (code "163") (name "unconnected-(L-A-Pad2)") (class "Default")
      (node (ref "L") (pin "2") (pinfunction "A_2") (pintype "passive"))
    )
    (net (code "164") (name "unconnected-(L-K-Pad1)") (class "Default")
      (node (ref "L") (pin "1") (pinfunction "K_1") (pintype "passive"))
    )
    (net (code "165") (name "unconnected-(L1-Pad1)") (class "Default")
      (node (ref "L1") (pin "1") (pinfunction "1_1") (pintype "passive"))
    )
    (net (code "166") (name "unconnected-(L1-Pad2)") (class "Default")
      (node (ref "L1") (pin "2") (pinfunction "2_2") (pintype "passive"))
    )
    (net (code "167") (name "unconnected-(L2-Pad1)") (class "Default")
      (node (ref "L2") (pin "1") (pinfunction "1_1") (pintype "passive"))
    )
    (net (code "168") (name "unconnected-(L2-Pad2)") (class "Default")
      (node (ref "L2") (pin "2") (pinfunction "2_2") (pintype "passive"))
    )
    (net (code "169") (name "unconnected-(ON-A-Pad2)") (class "Default")
      (node (ref "ON") (pin "2") (pinfunction "A_2") (pintype "passive"))
    )
    (net (code "170") (name "unconnected-(ON-K-Pad1)") (class "Default")
      (node (ref "ON") (pin "1") (pinfunction "K_1") (pintype "passive"))
    )
    (net (code "171") (name "unconnected-(R1-Pad1)") (class "Default")
      (node (ref "R1") (pin "1") (pinfunction "1_1") (pintype "passive"))
    )
    (net (code "172") (name "unconnected-(R1-Pad2)") (class "Default")
      (node (ref "R1") (pin "2") (pinfunction "2_2") (pintype "passive"))
    )
    (net (code "173") (name "unconnected-(R2-Pad1)") (class "Default")
      (node (ref "R2") (pin "1") (pinfunction "1_1") (pintype "passive"))
    )
    (net (code "174") (name "unconnected-(R2-Pad2)") (class "Default")
      (node (ref "R2") (pin "2") (pinfunction "2_2") (pintype "passive"))
    )
    (net (code "175") (name "unconnected-(RESET-Pad1)") (class "Default")
      (node (ref "RESET") (pin "1") (pinfunction "1_1") (pintype "passive"))
    )
    (net (code "176") (name "unconnected-(RESET-Pad2)") (class "Default")
      (node (ref "RESET") (pin "2") (pinfunction "2_2") (pintype "passive"))
    )
    (net (code "177") (name "unconnected-(RESET-Pad3)") (class "Default")
      (node (ref "RESET") (pin "3") (pinfunction "3_3") (pintype "passive"))
    )
    (net (code "178") (name "unconnected-(RESET-Pad4)") (class "Default")
      (node (ref "RESET") (pin "4") (pinfunction "4_4") (pintype "passive"))
    )
    (net (code "179") (name "unconnected-(RN1-Pad1)") (class "Default")
      (node (ref "RN1") (pin "1") (pinfunction "1_1") (pintype "passive"))
    )
    (net (code "180") (name "unconnected-(RN1-Pad2)") (class "Default")
      (node (ref "RN1") (pin "2") (pinfunction "2_2") (pintype "passive"))
    )
    (net (code "181") (name "unconnected-(RN1-Pad3)") (class "Default")
      (node (ref "RN1") (pin "3") (pinfunction "3_3") (pintype "passive"))
    )
    (net (code "182") (name "unconnected-(RN1-Pad4)") (class "Default")
      (node (ref "RN1") (pin "4") (pinfunction "4_4") (pintype "passive"))
    )
    (net (code "183") (name "unconnected-(RN1-Pad5)") (class "Default")
      (node (ref "RN1") (pin "5") (pinfunction "5_5") (pintype "passive"))
    )
    (net (code "184") (name "unconnected-(RN1-Pad6)") (class "Default")
      (node (ref "RN1") (pin "6") (pinfunction "6_6") (pintype "passive"))
    )
    (net (code "185") (name "unconnected-(RN1-Pad7)") (class "Default")
      (node (ref "RN1") (pin "7") (pinfunction "7_7") (pintype "passive"))
    )
    (net (code "186") (name "unconnected-(RN1-Pad8)") (class "Default")
      (node (ref "RN1") (pin "8") (pinfunction "8_8") (pintype "passive"))
    )
    (net (code "187") (name "unconnected-(RN2-Pad1)") (class "Default")
      (node (ref "RN2") (pin "1") (pinfunction "1_1") (pintype "passive"))
    )
    (net (code "188") (name "unconnected-(RN2-Pad2)") (class "Default")
      (node (ref "RN2") (pin "2") (pinfunction "2_2") (pintype "passive"))
    )
    (net (code "189") (name "unconnected-(RN2-Pad3)") (class "Default")
      (node (ref "RN2") (pin "3") (pinfunction "3_3") (pintype "passive"))
    )
    (net (code "190") (name "unconnected-(RN2-Pad4)") (class "Default")
      (node (ref "RN2") (pin "4") (pinfunction "4_4") (pintype "passive"))
    )
    (net (code "191") (name "unconnected-(RN2-Pad5)") (class "Default")
      (node (ref "RN2") (pin "5") (pinfunction "5_5") (pintype "passive"))
    )
    (net (code "192") (name "unconnected-(RN2-Pad6)") (class "Default")
      (node (ref "RN2") (pin "6") (pinfunction "6_6") (pintype "passive"))
    )
    (net (code "193") (name "unconnected-(RN2-Pad7)") (class "Default")
      (node (ref "RN2") (pin "7") (pinfunction "7_7") (pintype "passive"))
    )
    (net (code "194") (name "unconnected-(RN2-Pad8)") (class "Default")
      (node (ref "RN2") (pin "8") (pinfunction "8_8") (pintype "passive"))
    )
    (net (code "195") (name "unconnected-(RN3-Pad1)") (class "Default")
      (node (ref "RN3") (pin "1") (pinfunction "1_1") (pintype "passive"))
    )
    (net (code "196") (name "unconnected-(RN3-Pad2)") (class "Default")
      (node (ref "RN3") (pin "2") (pinfunction "2_2") (pintype "passive"))
    )
    (net (code "197") (name "unconnected-(RN3-Pad3)") (class "Default")
      (node (ref "RN3") (pin "3") (pinfunction "3_3") (pintype "passive"))
    )
    (net (code "198") (name "unconnected-(RN3-Pad4)") (class "Default")
      (node (ref "RN3") (pin "4") (pinfunction "4_4") (pintype "passive"))
    )
    (net (code "199") (name "unconnected-(RN3-Pad5)") (class "Default")
      (node (ref "RN3") (pin "5") (pinfunction "5_5") (pintype "passive"))
    )
    (net (code "200") (name "unconnected-(RN3-Pad6)") (class "Default")
      (node (ref "RN3") (pin "6") (pinfunction "6_6") (pintype "passive"))
    )
    (net (code "201") (name "unconnected-(RN3-Pad7)") (class "Default")
      (node (ref "RN3") (pin "7") (pinfunction "7_7") (pintype "passive"))
    )
    (net (code "202") (name "unconnected-(RN3-Pad8)") (class "Default")
      (node (ref "RN3") (pin "8") (pinfunction "8_8") (pintype "passive"))
    )
    (net (code "203") (name "unconnected-(RN4-Pad1)") (class "Default")
      (node (ref "RN4") (pin "1") (pinfunction "1_1") (pintype "passive"))
    )
    (net (code "204") (name "unconnected-(RN4-Pad2)") (class "Default")
      (node (ref "RN4") (pin "2") (pinfunction "2_2") (pintype "passive"))
    )
    (net (code "205") (name "unconnected-(RN4-Pad3)") (class "Default")
      (node (ref "RN4") (pin "3") (pinfunction "3_3") (pintype "passive"))
    )
    (net (code "206") (name "unconnected-(RN4-Pad4)") (class "Default")
      (node (ref "RN4") (pin "4") (pinfunction "4_4") (pintype "passive"))
    )
    (net (code "207") (name "unconnected-(RN4-Pad5)") (class "Default")
      (node (ref "RN4") (pin "5") (pinfunction "5_5") (pintype "passive"))
    )
    (net (code "208") (name "unconnected-(RN4-Pad6)") (class "Default")
      (node (ref "RN4") (pin "6") (pinfunction "6_6") (pintype "passive"))
    )
    (net (code "209") (name "unconnected-(RN4-Pad7)") (class "Default")
      (node (ref "RN4") (pin "7") (pinfunction "7_7") (pintype "passive"))
    )
    (net (code "210") (name "unconnected-(RN4-Pad8)") (class "Default")
      (node (ref "RN4") (pin "8") (pinfunction "8_8") (pintype "passive"))
    )
    (net (code "211") (name "unconnected-(RN5-Pad1)") (class "Default")
      (node (ref "RN5") (pin "1") (pinfunction "1_1") (pintype "passive"))
    )
    (net (code "212") (name "unconnected-(RN5-Pad2)") (class "Default")
      (node (ref "RN5") (pin "2") (pinfunction "2_2") (pintype "passive"))
    )
    (net (code "213") (name "unconnected-(RN5-Pad3)") (class "Default")
      (node (ref "RN5") (pin "3") (pinfunction "3_3") (pintype "passive"))
    )
    (net (code "214") (name "unconnected-(RN5-Pad4)") (class "Default")
      (node (ref "RN5") (pin "4") (pinfunction "4_4") (pintype "passive"))
    )
    (net (code "215") (name "unconnected-(RN5-Pad5)") (class "Default")
      (node (ref "RN5") (pin "5") (pinfunction "5_5") (pintype "passive"))
    )
    (net (code "216") (name "unconnected-(RN5-Pad6)") (class "Default")
      (node (ref "RN5") (pin "6") (pinfunction "6_6") (pintype "passive"))
    )
    (net (code "217") (name "unconnected-(RN5-Pad7)") (class "Default")
      (node (ref "RN5") (pin "7") (pinfunction "7_7") (pintype "passive"))
    )
    (net (code "218") (name "unconnected-(RN5-Pad8)") (class "Default")
      (node (ref "RN5") (pin "8") (pinfunction "8_8") (pintype "passive"))
    )
    (net (code "219") (name "unconnected-(RX-A-Pad2)") (class "Default")
      (node (ref "RX") (pin "2") (pinfunction "A_2") (pintype "passive"))
    )
    (net (code "220") (name "unconnected-(RX-K-Pad1)") (class "Default")
      (node (ref "RX") (pin "1") (pinfunction "K_1") (pintype "passive"))
    )
    (net (code "221") (name "unconnected-(TX-A-Pad2)") (class "Default")
      (node (ref "TX") (pin "2") (pinfunction "A_2") (pintype "passive"))
    )
    (net (code "222") (name "unconnected-(TX-K-Pad1)") (class "Default")
      (node (ref "TX") (pin "1") (pinfunction "K_1") (pintype "passive"))
    )
    (net (code "223") (name "unconnected-(Y1-C1-Pad1)") (class "Default")
      (node (ref "Y1") (pin "1") (pinfunction "C1_1") (pintype "passive"))
    )
    (net (code "224") (name "unconnected-(Y1-C2-Pad3)") (class "Default")
      (node (ref "Y1") (pin "3") (pinfunction "C2_3") (pintype "passive"))
    )
    (net (code "225") (name "unconnected-(Y1-GND-Pad2)") (class "Default")
      (node (ref "Y1") (pin "2") (pinfunction "GND_2") (pintype "power_in"))
    )
    (net (code "226") (name "unconnected-(Z1-Pad1)") (class "Default")
      (node (ref "Z1") (pin "1") (pinfunction "1_1") (pintype "passive"))
    )
    (net (code "227") (name "unconnected-(Z1-Pad2)") (class "Default")
      (node (ref "Z1") (pin "2") (pinfunction "2_2") (pintype "passive"))
    )
    (net (code "228") (name "unconnected-(Z2-Pad1)") (class "Default")
      (node (ref "Z2") (pin "1") (pinfunction "1_1") (pintype "passive"))
    )
    (net (code "229") (name "unconnected-(Z2-Pad2)") (class "Default")
      (node (ref "Z2") (pin "2") (pinfunction "2_2") (pintype "passive"))
    )
  )
)
